# ControlDSP.net
KiCad netlist of a schematic drawn in Altium Designer
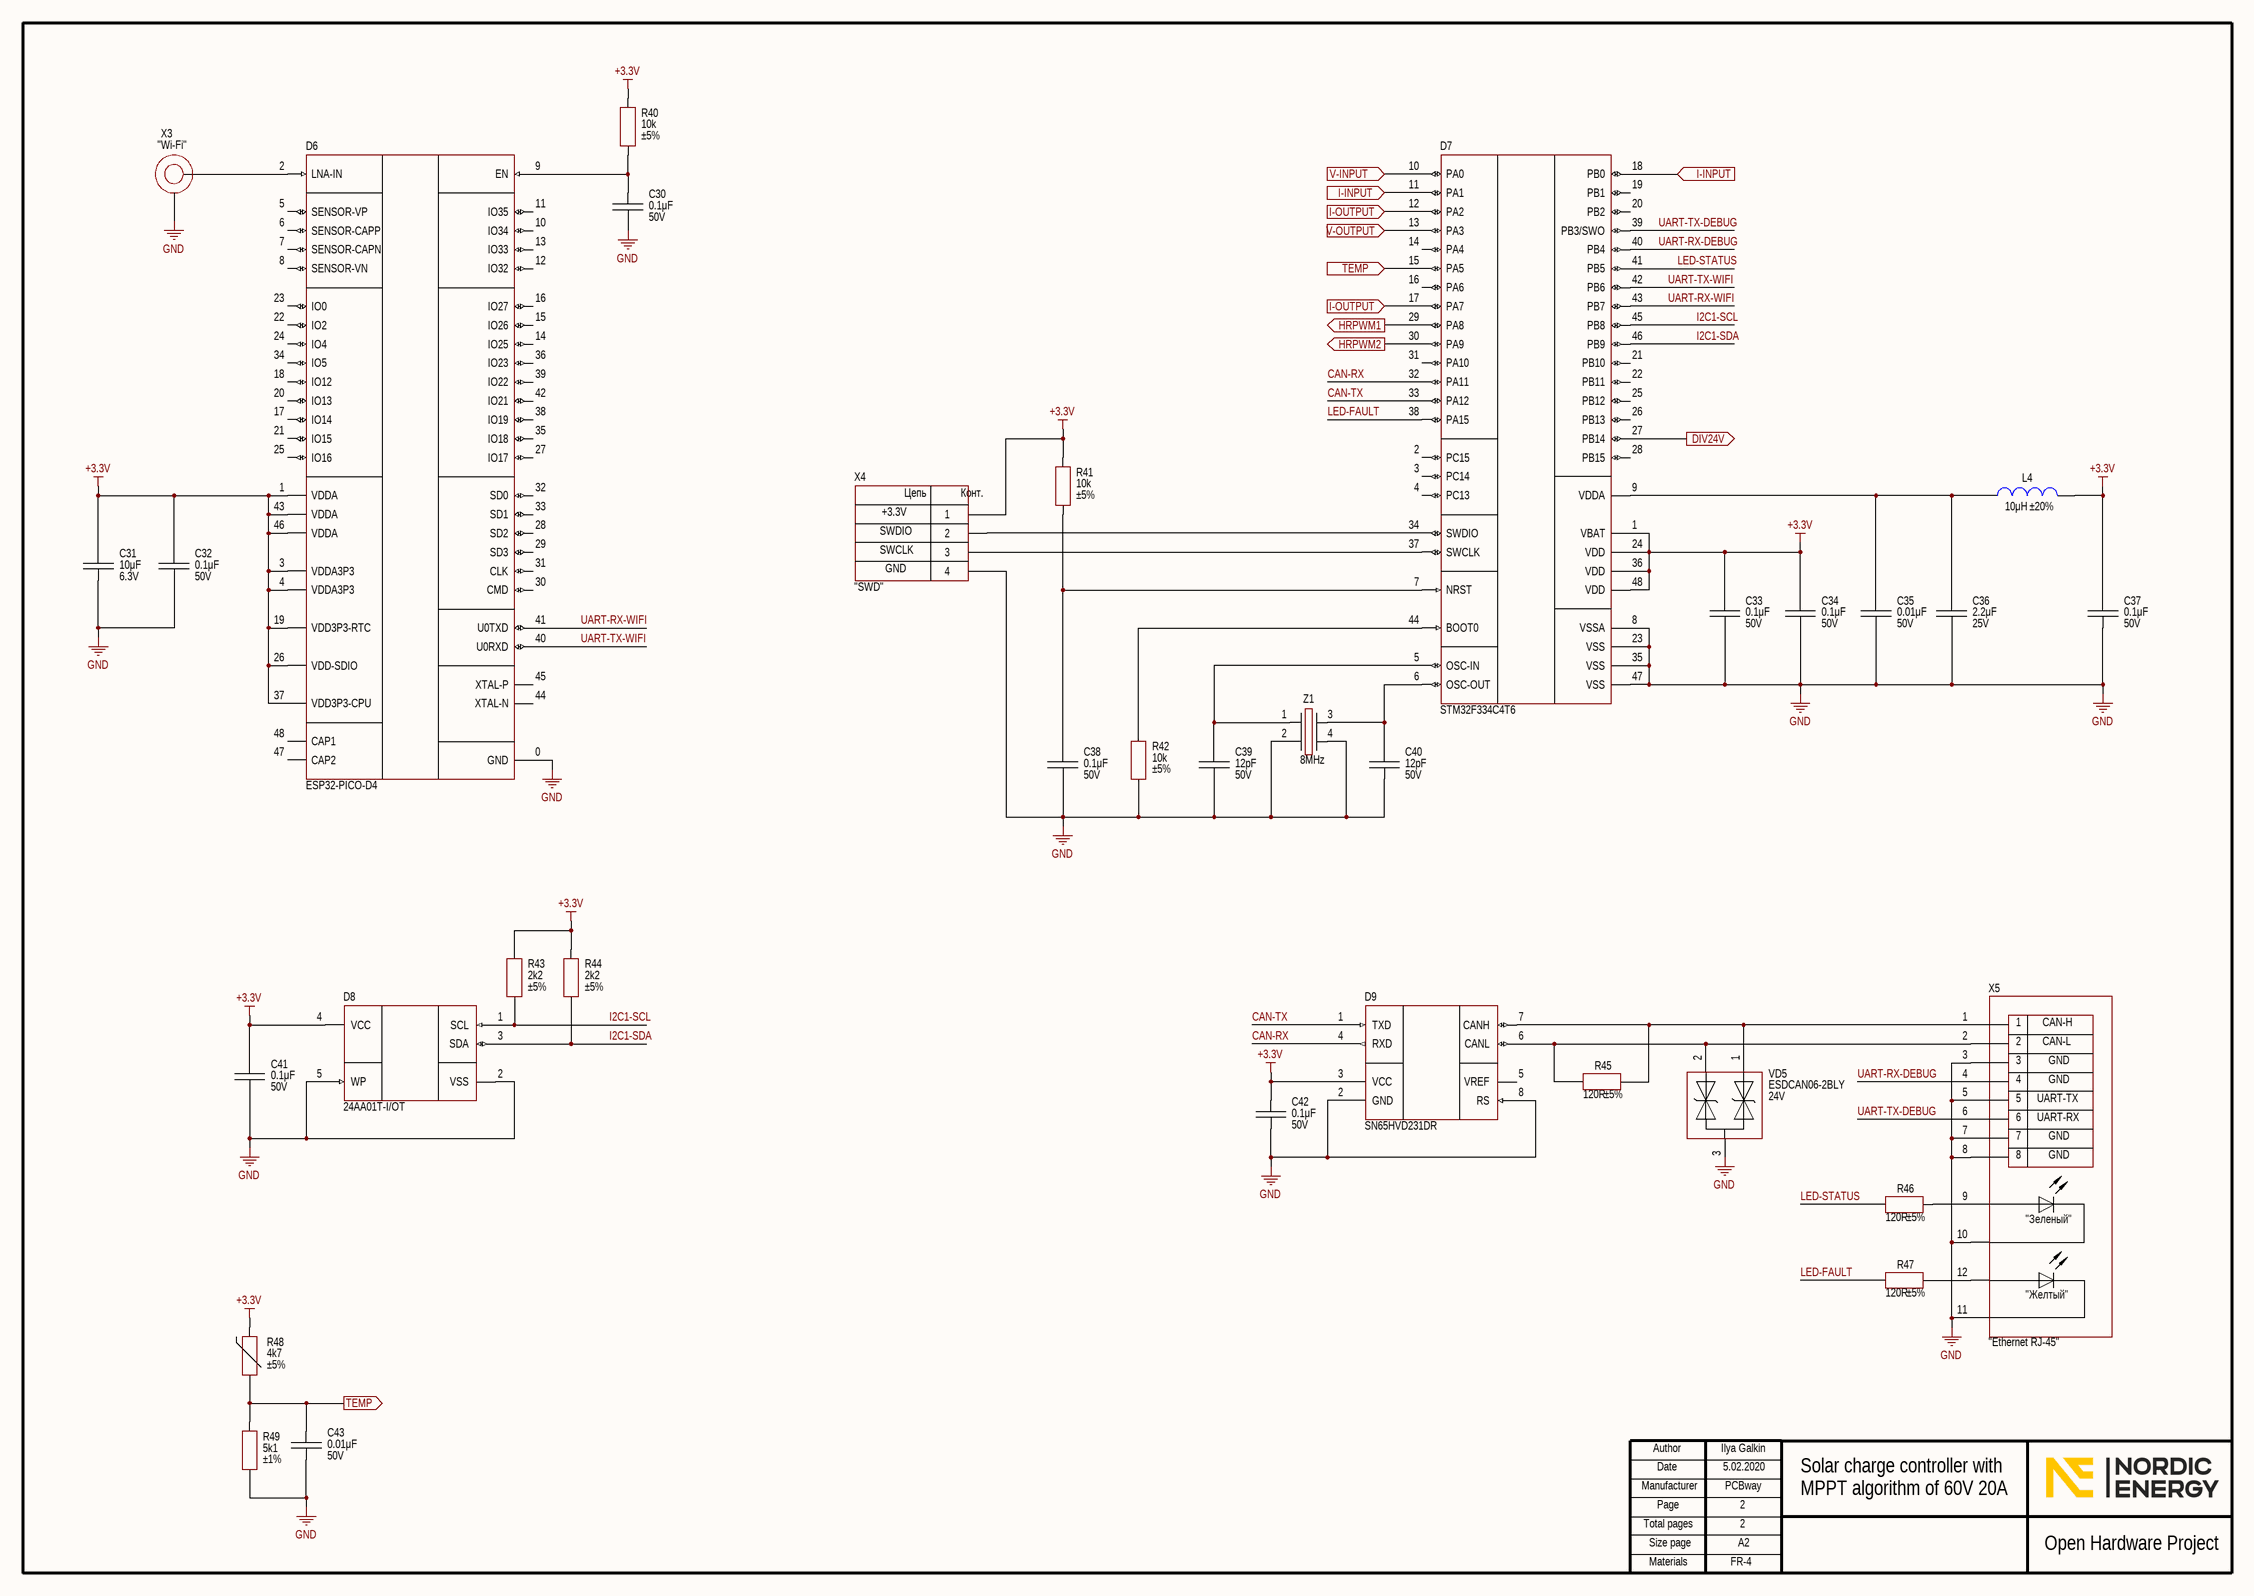
[diagram p0: ControlDSP.SchDoc]

(export (version "E")
  (design (tool "Eeschema 10.0.6"))
  (components
    (comp (ref "C30")
      (value "0.1μF")
      (footprint "CAP: 0805")
      (fields
        (field (name "MANUFACTURER") "Samsung")
        (field (name "PARTNUMBER") "CL21B104KBCNFNC")
        (field (name "VALUEMANUFACTURERPARTNUMBER") "Ceramic capacitor, 0.1μF, X7R, ±10%, 50V, 0805, -55...+125°C")
        (field (name "VOLTAGE") "50V")
      )
      (libsource (lib "Capacitor") (part "Ceramic_0805"))
    )
    (comp (ref "C31")
      (value "10μF")
      (footprint "CAP: 0805")
      (fields
        (field (name "MANUFACTURER") "Samsung")
        (field (name "PARTNUMBER") "CL21B106KQQNNNG")
        (field (name "VALUEMANUFACTURERPARTNUMBER") "Ceramic capacitor, 10μF, X7R, ±10%, 6.3V, 0805, -55...+125°C")
        (field (name "VOLTAGE") "6.3V")
      )
      (libsource (lib "Capacitor") (part "Ceramic_0805"))
    )
    (comp (ref "C32")
      (value "0.1μF")
      (footprint "CAP: 0805")
      (fields
        (field (name "MANUFACTURER") "Samsung")
        (field (name "PARTNUMBER") "CL21B104KBCNFNC")
        (field (name "VALUEMANUFACTURERPARTNUMBER") "Ceramic capacitor, 0.1μF, X7R, ±10%, 50V, 0805, -55...+125°C")
        (field (name "VOLTAGE") "50V")
      )
      (libsource (lib "Capacitor") (part "Ceramic_0805"))
    )
    (comp (ref "C33")
      (value "0.1μF")
      (footprint "CAP: 0805")
      (fields
        (field (name "MANUFACTURER") "Samsung")
        (field (name "PARTNUMBER") "CL21B104KBCNFNC")
        (field (name "VALUEMANUFACTURERPARTNUMBER") "Ceramic capacitor, 0.1μF, X7R, ±10%, 50V, 0805, -55...+125°C")
        (field (name "VOLTAGE") "50V")
      )
      (libsource (lib "Capacitor") (part "Ceramic_0805"))
    )
    (comp (ref "C34")
      (value "0.1μF")
      (footprint "CAP: 0805")
      (fields
        (field (name "MANUFACTURER") "Samsung")
        (field (name "PARTNUMBER") "CL21B104KBCNFNC")
        (field (name "VALUEMANUFACTURERPARTNUMBER") "Ceramic capacitor, 0.1μF, X7R, ±10%, 50V, 0805, -55...+125°C")
        (field (name "VOLTAGE") "50V")
      )
      (libsource (lib "Capacitor") (part "Ceramic_0805"))
    )
    (comp (ref "C35")
      (value "0.01μF")
      (footprint "CAP: 0805")
      (fields
        (field (name "MANUFACTURER") "Samsung")
        (field (name "PARTNUMBER") "CL21B103KBANNNC")
        (field (name "VALUEMANUFACTURERPARTNUMBER") "Ceramic capacitor, 0.01μF, X7R, ±10%, 50V, 0805, -55...+125°C")
        (field (name "VOLTAGE") "50V")
      )
      (libsource (lib "Capacitor") (part "Ceramic_0805"))
    )
    (comp (ref "C36")
      (value "2.2μF")
      (footprint "CAP: 0805")
      (fields
        (field (name "MANUFACTURER") "Samsung")
        (field (name "PARTNUMBER") "CL21B225KAFNFNE")
        (field (name "VALUEMANUFACTURERPARTNUMBER") "Ceramic capacitor, 2.2μF, X7R, ±10%, 25V, 0805, -55...+125°C")
        (field (name "VOLTAGE") "25V")
      )
      (libsource (lib "Capacitor") (part "Ceramic_0805"))
    )
    (comp (ref "C37")
      (value "0.1μF")
      (footprint "CAP: 0805")
      (fields
        (field (name "MANUFACTURER") "Samsung")
        (field (name "PARTNUMBER") "CL21B104KBCNFNC")
        (field (name "VALUEMANUFACTURERPARTNUMBER") "Ceramic capacitor, 0.1μF, X7R, ±10%, 50V, 0805, -55...+125°C")
        (field (name "VOLTAGE") "50V")
      )
      (libsource (lib "Capacitor") (part "Ceramic_0805"))
    )
    (comp (ref "C38")
      (value "0.1μF")
      (footprint "CAP: 0805")
      (fields
        (field (name "MANUFACTURER") "Samsung")
        (field (name "PARTNUMBER") "CL21B104KBCNFNC")
        (field (name "VALUEMANUFACTURERPARTNUMBER") "Ceramic capacitor, 0.1μF, X7R, ±10%, 50V, 0805, -55...+125°C")
        (field (name "VOLTAGE") "50V")
      )
      (libsource (lib "Capacitor") (part "Ceramic_0805"))
    )
    (comp (ref "C39")
      (value "12pF")
      (footprint "CAP: 0805")
      (fields
        (field (name "MANUFACTURER") "Samsung")
        (field (name "PARTNUMBER") "CL21C120JBANNNC")
        (field (name "VALUEMANUFACTURERPARTNUMBER") "Ceramic capacitor, 12pF, NPO, ±5%, 50V, 0805, -55...+125°C")
        (field (name "VOLTAGE") "50V")
      )
      (libsource (lib "Capacitor") (part "Ceramic_0805"))
    )
    (comp (ref "C40")
      (value "12pF")
      (footprint "CAP: 0805")
      (fields
        (field (name "MANUFACTURER") "Samsung")
        (field (name "PARTNUMBER") "CL21C120JBANNNC")
        (field (name "VALUEMANUFACTURERPARTNUMBER") "Ceramic capacitor, 12pF, NPO, ±5%, 50V, 0805, -55...+125°C")
        (field (name "VOLTAGE") "50V")
      )
      (libsource (lib "Capacitor") (part "Ceramic_0805"))
    )
    (comp (ref "C41")
      (value "0.1μF")
      (footprint "CAP: 0805")
      (fields
        (field (name "MANUFACTURER") "Samsung")
        (field (name "PARTNUMBER") "CL21B104KBCNFNC")
        (field (name "VALUEMANUFACTURERPARTNUMBER") "Ceramic capacitor, 0.1μF, X7R, ±10%, 50V, 0805, -55...+125°C")
        (field (name "VOLTAGE") "50V")
      )
      (libsource (lib "Capacitor") (part "Ceramic_0805"))
    )
    (comp (ref "C42")
      (value "0.1μF")
      (footprint "CAP: 0805")
      (fields
        (field (name "MANUFACTURER") "Samsung")
        (field (name "PARTNUMBER") "CL21B104KBCNFNC")
        (field (name "VALUEMANUFACTURERPARTNUMBER") "Ceramic capacitor, 0.1μF, X7R, ±10%, 50V, 0805, -55...+125°C")
        (field (name "VOLTAGE") "50V")
      )
      (libsource (lib "Capacitor") (part "Ceramic_0805"))
    )
    (comp (ref "C43")
      (value "0.01μF")
      (footprint "CAP: 0805")
      (fields
        (field (name "MANUFACTURER") "Samsung")
        (field (name "PARTNUMBER") "CL21B103KBANNNC")
        (field (name "VALUEMANUFACTURERPARTNUMBER") "Ceramic capacitor, 0.01μF, X7R, ±10%, 50V, 0805, -55...+125°C")
        (field (name "VOLTAGE") "50V")
      )
      (libsource (lib "Capacitor") (part "Ceramic_0805"))
    )
    (comp (ref "D6")
      (value "~")
      (footprint "48-LGA (7x7)")
      (description "Wi-Fi+BT")
      (fields (field (name "MANUFACTURER") "Espressif Systems") (field (name "PARTNUMBER") "ESP32-PICO-D4"))
      (libsource (lib "IC. RF transceiver") (part "ESP32-PICO-D4"))
    )
    (comp (ref "D7")
      (value "~")
      (footprint "48-LQFP")
      (description "Cortex-M4")
      (fields
        (field (name "MANUFACTURER") "STMicroelectronics")
        (field (name "VALUEMANUFACTURERPARTNUMBER") "IC microcontroller, 32-Bit, Cortex-M4, 72MHz, 16KB, 12KB, 2...3.6V, -40...+85°C, 48-LQFP")
        (field (name "PARTNUMBER") "STM32F334C4T6")
      )
      (libsource (lib "IC. MCU") (part "STM32F334C4T6"))
    )
    (comp (ref "D8")
      (value "~")
      (footprint "SOT23-5")
      (description "EEPROM")
      (fields
        (field (name "MANUFACTURER") "Microchip Technology")
        (field (name "VALUEMANUFACTURERPARTNUMBER") "IC memory, EEPROM, 1KB (128x8), 400 kHz, I2C, 1.7...5.5V, -40...+85°C, SOT-23-5")
        (field (name "PARTNUMBER") "24AA01T-I/OT")
      )
      (libsource (lib "IC. Memory") (part "24AA01T"))
    )
    (comp (ref "D9")
      (value "~")
      (footprint "8-SOIC")
      (description "CAN")
      (fields
        (field (name "MANUFACTURER") "Texas Instruments")
        (field (name "VALUEMANUFACTURERPARTNUMBER") "IC CAN transceiver, 1Mbps, Half-duplex, 3...3.6V, -40...+85°C, 8-SOIC")
        (field (name "PARTNUMBER") "SN65HVD231DR")
      )
      (libsource (lib "IC. Interface") (part "SN65HVD231DR"))
    )
    (comp (ref "L4")
      (value "10μH")
      (footprint "IND: 0805")
      (fields
        (field (name "MANUFACTURER") "Murata Electronics")
        (field (name "PARTNUMBER") "LQM21DH100M70L")
        (field (name "VALUEMANUFACTURERPARTNUMBER") "Fixed inductor, 10μH, ±20%, 0805, 250mA, -55...+125°C")
        (field (name "TOLERANCE") "±20%")
      )
      (libsource (lib "Inductor") (part "Inductor_0805"))
    )
    (comp (ref "R40")
      (value "10k")
      (footprint "RES: 0805")
      (fields
        (field (name "MANUFACTURER") "Yageo")
        (field (name "PARTNUMBER") "RC0805JR-0710KL")
        (field (name "VALUEMANUFACTURERPARTNUMBER") "Resistor film, 10k, ±5%, 0805, 0.125W, -55...+125°C")
        (field (name "TOLERANCE") "±5%")
      )
      (libsource (lib "Resistor") (part "Resistor_0805"))
    )
    (comp (ref "R41")
      (value "10k")
      (footprint "RES: 0805")
      (fields
        (field (name "MANUFACTURER") "Yageo")
        (field (name "PARTNUMBER") "RC0805JR-0710KL")
        (field (name "VALUEMANUFACTURERPARTNUMBER") "Resistor film, 10k, ±5%, 0805, 0.125W, -55...+125°C")
        (field (name "TOLERANCE") "±5%")
      )
      (libsource (lib "Resistor") (part "Resistor_0805"))
    )
    (comp (ref "R42")
      (value "10k")
      (footprint "RES: 0805")
      (fields
        (field (name "MANUFACTURER") "Yageo")
        (field (name "PARTNUMBER") "RC0805JR-0710KL")
        (field (name "VALUEMANUFACTURERPARTNUMBER") "Resistor film, 10k, ±5%, 0805, 0.125W, -55...+125°C")
        (field (name "TOLERANCE") "±5%")
      )
      (libsource (lib "Resistor") (part "Resistor_0805"))
    )
    (comp (ref "R43")
      (value "2k2")
      (footprint "RES: 0805")
      (fields
        (field (name "MANUFACTURER") "Yageo")
        (field (name "PARTNUMBER") "RC0805JR-072K2L")
        (field (name "VALUEMANUFACTURERPARTNUMBER") "Resistor film, 2k2, ±5%, 0805, 0.125W, -55...+125°C")
        (field (name "TOLERANCE") "±5%")
      )
      (libsource (lib "Resistor") (part "Resistor_0805"))
    )
    (comp (ref "R44")
      (value "2k2")
      (footprint "RES: 0805")
      (fields
        (field (name "MANUFACTURER") "Yageo")
        (field (name "PARTNUMBER") "RC0805JR-072K2L")
        (field (name "VALUEMANUFACTURERPARTNUMBER") "Resistor film, 2k2, ±5%, 0805, 0.125W, -55...+125°C")
        (field (name "TOLERANCE") "±5%")
      )
      (libsource (lib "Resistor") (part "Resistor_0805"))
    )
    (comp (ref "R45")
      (value "120R")
      (footprint "RES: 0805")
      (fields
        (field (name "MANUFACTURER") "Yageo")
        (field (name "PARTNUMBER") "RC0805JR-07120RL")
        (field (name "VALUEMANUFACTURERPARTNUMBER") "Resistor film, 120R, ±5%, 0805, 0.125W, -55...+125°C")
        (field (name "TOLERANCE") "±5%")
      )
      (libsource (lib "") (part "Resistor_0805_1"))
    )
    (comp (ref "R46")
      (value "120R")
      (footprint "RES: 0805")
      (fields
        (field (name "MANUFACTURER") "Yageo")
        (field (name "PARTNUMBER") "RC0805JR-07120RL")
        (field (name "VALUEMANUFACTURERPARTNUMBER") "Resistor film, 120R, ±5%, 0805, 0.125W, -55...+125°C")
        (field (name "TOLERANCE") "±5%")
      )
      (libsource (lib "") (part "Resistor_0805_1"))
    )
    (comp (ref "R47")
      (value "120R")
      (footprint "RES: 0805")
      (fields
        (field (name "MANUFACTURER") "Yageo")
        (field (name "PARTNUMBER") "RC0805JR-07120RL")
        (field (name "VALUEMANUFACTURERPARTNUMBER") "Resistor film, 120R, ±5%, 0805, 0.125W, -55...+125°C")
        (field (name "TOLERANCE") "±5%")
      )
      (libsource (lib "") (part "Resistor_0805_1"))
    )
    (comp (ref "R48")
      (value "4k7")
      (footprint "RES: 0805")
      (fields
        (field (name "MANUFACTURER") "TDK")
        (field (name "PARTNUMBER") "B57401V2472J062")
        (field (name "VALUEMANUFACTURERPARTNUMBER") "NTC resistor, 4k7, ±5%, 0805, 3650K, -55...+125°C")
        (field (name "TOLERANCE") "±5%")
      )
      (libsource (lib "Resistor") (part "NTC"))
    )
    (comp (ref "R49")
      (value "5k1")
      (footprint "RES: 0805")
      (fields
        (field (name "MANUFACTURER") "Yageo")
        (field (name "PARTNUMBER") "RC0805FR-075K1L")
        (field (name "VALUEMANUFACTURERPARTNUMBER") "Resistor film, 5k1, ±1%, 0805, 0.125W, -55...+125°C")
        (field (name "TOLERANCE") "±1%")
      )
      (libsource (lib "Resistor") (part "Resistor_0805"))
    )
    (comp (ref "VD5")
      (value "~")
      (footprint "SOT23")
      (fields
        (field (name "MANUFACTURER") "STMicroelectronics")
        (field (name "VALUEMANUFACTURERPARTNUMBER") "TVS diode, 24V, 230W peak, 3A, 13pF, SOT-23, -40...+150°C")
        (field (name "VOLTAGE") "24V")
        (field (name "PARTNUMBER") "ESDCAN06-2BLY")
      )
      (libsource (lib "Diode") (part "TVS_array"))
    )
    (comp (ref "X3")
      (value "~")
      (footprint "CON: u.Fl")
      (fields
        (field (name "MANUFACTURER") "Hirose Electric")
        (field (name "VALUEMANUFACTURERPARTNUMBER") "Connector u.FL, 50 Ohm, 6GHz")
        (field (name "PARTNUMBER") "U.FL-R-SMT(01)")
        (field (name "COMMENTTEXT") "\"Wi-Fi\"")
      )
      (libsource (lib "Connector") (part "Connector_uFL"))
    )
    (comp (ref "X4")
      (value "~")
      (footprint "CON: SM04B-GHS")
      (fields
        (field (name "MANUFACTURER") "JST")
        (field (name "VALUEMANUFACTURERPARTNUMBER") "Connector, 4pin, 1.25mm, 50VDC, 1A")
        (field (name "PARTNUMBER") "SM04B-GHS")
        (field (name "COMMENTTEXT") "\"SWD\"")
      )
      (libsource (lib "Connector") (part "Connector_SM04B"))
    )
    (comp (ref "X5")
      (value "~")
      (footprint "CON: RJ-45 (615008137421 / DS1128-09-S8B8S)")
      (fields
        (field (name "MANUFACTURER") "Wurth")
        (field (name "VALUEMANUFACTURERPARTNUMBER") "Etherner RJ-45 connector")
        (field (name "PARTNUMBER") "615008137421")
        (field (name "COMMENTTEXT") "\"Ethernet RJ-45\"")
      )
      (libsource (lib "Connector") (part "Connector_RJ45"))
    )
    (comp (ref "Z1")
      (value "~")
      (footprint "OSC: 3225")
      (fields
        (field (name "MANUFACTURER") "ECS")
        (field (name "PARTNUMBER") "ECS-80-12-33-JGN-TR")
        (field (name "VALUEMANUFACTURERPARTNUMBER") "Crystal, 8MHz, 12pF, ±30ppm, case 3225, -40...+85°C")
        (field (name "FREQUENCY") "8MHz")
      )
      (libsource (lib "Oscilator") (part "Crystal_3225"))
    )
  )
  (nets
    (net (code "1") (name "+3.3V") (class "Default")
      (node (ref "C31") (pin "2") (pinfunction "2_2") (pintype "power_in"))
      (node (ref "C32") (pin "2") (pinfunction "2_2") (pintype "power_in"))
      (node (ref "C33") (pin "2") (pinfunction "2_2") (pintype "power_in"))
      (node (ref "C34") (pin "2") (pinfunction "2_2") (pintype "power_in"))
      (node (ref "C37") (pin "2") (pinfunction "2_2") (pintype "power_in"))
      (node (ref "C41") (pin "2") (pinfunction "2_2") (pintype "power_in"))
      (node (ref "C42") (pin "2") (pinfunction "2_2") (pintype "power_in"))
      (node (ref "D6") (pin "1") (pinfunction "VDDA_1") (pintype "passive"))
      (node (ref "D6") (pin "19") (pinfunction "VDD3P3-RTC_19") (pintype "passive"))
      (node (ref "D6") (pin "26") (pinfunction "VDD-SDIO_26") (pintype "passive"))
      (node (ref "D6") (pin "3") (pinfunction "VDDA3P3_3") (pintype "passive"))
      (node (ref "D6") (pin "37") (pinfunction "VDD3P3-CPU_37") (pintype "passive"))
      (node (ref "D6") (pin "4") (pinfunction "VDDA3P3_4") (pintype "passive"))
      (node (ref "D6") (pin "43") (pinfunction "VDDA_43") (pintype "passive"))
      (node (ref "D6") (pin "46") (pinfunction "VDDA_46") (pintype "passive"))
      (node (ref "D7") (pin "1") (pinfunction "VBAT_1") (pintype "passive"))
      (node (ref "D7") (pin "24") (pinfunction "VDD_24") (pintype "passive"))
      (node (ref "D7") (pin "36") (pinfunction "VDD_36") (pintype "passive"))
      (node (ref "D7") (pin "48") (pinfunction "VDD_48") (pintype "passive"))
      (node (ref "D8") (pin "4") (pinfunction "VCC_4") (pintype "power_in"))
      (node (ref "D9") (pin "3") (pinfunction "VCC_3") (pintype "passive"))
      (node (ref "L4") (pin "1") (pinfunction "1_1") (pintype "passive"))
      (node (ref "R40") (pin "2") (pinfunction "2_2") (pintype "passive"))
      (node (ref "R41") (pin "2") (pinfunction "2_2") (pintype "passive"))
      (node (ref "R43") (pin "2") (pinfunction "2_2") (pintype "passive"))
      (node (ref "R44") (pin "2") (pinfunction "2_2") (pintype "passive"))
      (node (ref "R48") (pin "2") (pinfunction "2_2") (pintype "passive"))
      (node (ref "X4") (pin "1") (pinfunction "1_1") (pintype "passive"))
    )
    (net (code "2") (name "/CAN-RX") (class "Default")
      (node (ref "D7") (pin "32") (pinfunction "PA11_32") (pintype "bidirectional"))
      (node (ref "D9") (pin "4") (pinfunction "RXD_4") (pintype "output"))
    )
    (net (code "3") (name "/CAN-TX") (class "Default")
      (node (ref "D7") (pin "33") (pinfunction "PA12_33") (pintype "bidirectional"))
      (node (ref "D9") (pin "1") (pinfunction "TXD_1") (pintype "input"))
    )
    (net (code "4") (name "/DIV24V") (class "Default")
      (node (ref "D7") (pin "27") (pinfunction "PB14_27") (pintype "bidirectional"))
    )
    (net (code "5") (name "/HRPWM1") (class "Default")
      (node (ref "D7") (pin "29") (pinfunction "PA8_29") (pintype "bidirectional"))
    )
    (net (code "6") (name "/HRPWM2") (class "Default")
      (node (ref "D7") (pin "30") (pinfunction "PA9_30") (pintype "bidirectional"))
    )
    (net (code "7") (name "/I-INPUT") (class "Default")
      (node (ref "D7") (pin "11") (pinfunction "PA1_11") (pintype "bidirectional"))
      (node (ref "D7") (pin "18") (pinfunction "PB0_18") (pintype "bidirectional"))
    )
    (net (code "8") (name "/I-OUTPUT") (class "Default")
      (node (ref "D7") (pin "12") (pinfunction "PA2_12") (pintype "bidirectional"))
      (node (ref "D7") (pin "17") (pinfunction "PA7_17") (pintype "bidirectional"))
    )
    (net (code "9") (name "/I2C1-SCL") (class "Default")
      (node (ref "D7") (pin "45") (pinfunction "PB8_45") (pintype "bidirectional"))
      (node (ref "D8") (pin "1") (pinfunction "SCL_1") (pintype "input"))
      (node (ref "R43") (pin "1") (pinfunction "1_1") (pintype "passive"))
    )
    (net (code "10") (name "/I2C1-SDA") (class "Default")
      (node (ref "D7") (pin "46") (pinfunction "PB9_46") (pintype "bidirectional"))
      (node (ref "D8") (pin "3") (pinfunction "SDA_3") (pintype "bidirectional"))
      (node (ref "R44") (pin "1") (pinfunction "1_1") (pintype "passive"))
    )
    (net (code "11") (name "/LED-FAULT") (class "Default")
      (node (ref "D7") (pin "38") (pinfunction "PA15_38") (pintype "bidirectional"))
      (node (ref "R47") (pin "2") (pinfunction "2_2") (pintype "passive"))
    )
    (net (code "12") (name "/LED-STATUS") (class "Default")
      (node (ref "D7") (pin "41") (pinfunction "PB5_41") (pintype "bidirectional"))
      (node (ref "R46") (pin "2") (pinfunction "2_2") (pintype "passive"))
    )
    (net (code "13") (name "/TEMP") (class "Default")
      (node (ref "C43") (pin "2") (pinfunction "2_2") (pintype "power_in"))
      (node (ref "D7") (pin "15") (pinfunction "PA5_15") (pintype "bidirectional"))
      (node (ref "R48") (pin "1") (pinfunction "1_1") (pintype "passive"))
      (node (ref "R49") (pin "2") (pinfunction "2_2") (pintype "passive"))
    )
    (net (code "14") (name "/UART-RX-DEBUG") (class "Default")
      (node (ref "D7") (pin "40") (pinfunction "PB4_40") (pintype "bidirectional"))
      (node (ref "X5") (pin "4") (pinfunction "D2_4") (pintype "passive"))
    )
    (net (code "15") (name "/UART-RX-WIFI") (class "Default")
      (node (ref "D6") (pin "41") (pinfunction "U0TXD_41") (pintype "bidirectional"))
      (node (ref "D7") (pin "43") (pinfunction "PB7_43") (pintype "bidirectional"))
    )
    (net (code "16") (name "/UART-TX-DEBUG") (class "Default")
      (node (ref "D7") (pin "39") (pinfunction "PB3/SWO_39") (pintype "bidirectional"))
      (node (ref "X5") (pin "6") (pinfunction "D2_6") (pintype "passive"))
    )
    (net (code "17") (name "/UART-TX-WIFI") (class "Default")
      (node (ref "D6") (pin "40") (pinfunction "U0RXD_40") (pintype "bidirectional"))
      (node (ref "D7") (pin "42") (pinfunction "PB6_42") (pintype "bidirectional"))
    )
    (net (code "18") (name "/V-INPUT") (class "Default")
      (node (ref "D7") (pin "10") (pinfunction "PA0_10") (pintype "bidirectional"))
    )
    (net (code "19") (name "/V-OUTPUT") (class "Default")
      (node (ref "D7") (pin "13") (pinfunction "PA3_13") (pintype "bidirectional"))
    )
    (net (code "20") (name "GND") (class "Default")
      (node (ref "C30") (pin "1") (pinfunction "1_1") (pintype "power_in"))
      (node (ref "C31") (pin "1") (pinfunction "1_1") (pintype "power_in"))
      (node (ref "C32") (pin "1") (pinfunction "1_1") (pintype "power_in"))
      (node (ref "C33") (pin "1") (pinfunction "1_1") (pintype "power_in"))
      (node (ref "C34") (pin "1") (pinfunction "1_1") (pintype "power_in"))
      (node (ref "C35") (pin "1") (pinfunction "1_1") (pintype "power_in"))
      (node (ref "C36") (pin "1") (pinfunction "1_1") (pintype "power_in"))
      (node (ref "C37") (pin "1") (pinfunction "1_1") (pintype "power_in"))
      (node (ref "C38") (pin "1") (pinfunction "1_1") (pintype "power_in"))
      (node (ref "C39") (pin "1") (pinfunction "1_1") (pintype "power_in"))
      (node (ref "C40") (pin "1") (pinfunction "1_1") (pintype "power_in"))
      (node (ref "C41") (pin "1") (pinfunction "1_1") (pintype "power_in"))
      (node (ref "C42") (pin "1") (pinfunction "1_1") (pintype "power_in"))
      (node (ref "C43") (pin "1") (pinfunction "1_1") (pintype "power_in"))
      (node (ref "D6") (pin "0") (pinfunction "GND_0") (pintype "passive"))
      (node (ref "D7") (pin "23") (pinfunction "VSS_23") (pintype "passive"))
      (node (ref "D7") (pin "35") (pinfunction "VSS_35") (pintype "passive"))
      (node (ref "D7") (pin "47") (pinfunction "VSS_47") (pintype "passive"))
      (node (ref "D7") (pin "8") (pinfunction "VSSA_8") (pintype "passive"))
      (node (ref "D8") (pin "2") (pinfunction "VSS_2") (pintype "power_in"))
      (node (ref "D8") (pin "5") (pinfunction "WP_5") (pintype "input"))
      (node (ref "D9") (pin "2") (pinfunction "GND_2") (pintype "passive"))
      (node (ref "D9") (pin "8") (pinfunction "RS_8") (pintype "input"))
      (node (ref "R42") (pin "1") (pinfunction "1_1") (pintype "passive"))
      (node (ref "R49") (pin "1") (pinfunction "1_1") (pintype "passive"))
      (node (ref "VD5") (pin "3") (pintype "passive"))
      (node (ref "X3") (pin "2") (pinfunction "2_2") (pintype "passive"))
      (node (ref "X4") (pin "4") (pinfunction "4_4") (pintype "power_in"))
      (node (ref "X5") (pin "10") (pinfunction "D1_10") (pintype "passive"))
      (node (ref "X5") (pin "11") (pinfunction "D3_11") (pintype "passive"))
      (node (ref "X5") (pin "3") (pinfunction "D2_3") (pintype "passive"))
      (node (ref "X5") (pin "5") (pinfunction "D2_5") (pintype "passive"))
      (node (ref "X5") (pin "7") (pinfunction "D2_7") (pintype "passive"))
      (node (ref "X5") (pin "8") (pinfunction "D2_8") (pintype "passive"))
      (node (ref "Z1") (pin "2") (pinfunction "2_2") (pintype "passive"))
      (node (ref "Z1") (pin "4") (pinfunction "4_4") (pintype "passive"))
    )
    (net (code "21") (name "Net-(D6-EN)") (class "Default")
      (node (ref "C30") (pin "2") (pinfunction "2_2") (pintype "power_in"))
      (node (ref "D6") (pin "9") (pinfunction "EN_9") (pintype "input"))
      (node (ref "R40") (pin "1") (pinfunction "1_1") (pintype "passive"))
    )
    (net (code "22") (name "Net-(D6-LNA-IN)") (class "Default")
      (node (ref "D6") (pin "2") (pinfunction "LNA-IN_2") (pintype "input"))
      (node (ref "X3") (pin "1") (pinfunction "1_1") (pintype "passive"))
    )
    (net (code "23") (name "Net-(D7-BOOT0)") (class "Default")
      (node (ref "D7") (pin "44") (pinfunction "BOOT0_44") (pintype "input"))
      (node (ref "R42") (pin "2") (pinfunction "2_2") (pintype "passive"))
    )
    (net (code "24") (name "Net-(D7-NRST)") (class "Default")
      (node (ref "C38") (pin "2") (pinfunction "2_2") (pintype "power_in"))
      (node (ref "D7") (pin "7") (pinfunction "NRST_7") (pintype "input"))
      (node (ref "R41") (pin "1") (pinfunction "1_1") (pintype "passive"))
    )
    (net (code "25") (name "Net-(D7-OSC-IN)") (class "Default")
      (node (ref "C39") (pin "2") (pinfunction "2_2") (pintype "power_in"))
      (node (ref "D7") (pin "5") (pinfunction "OSC-IN_5") (pintype "bidirectional"))
      (node (ref "Z1") (pin "1") (pinfunction "1_1") (pintype "passive"))
    )
    (net (code "26") (name "Net-(D7-OSC-OUT)") (class "Default")
      (node (ref "C40") (pin "2") (pinfunction "2_2") (pintype "power_in"))
      (node (ref "D7") (pin "6") (pinfunction "OSC-OUT_6") (pintype "bidirectional"))
      (node (ref "Z1") (pin "3") (pinfunction "3_3") (pintype "passive"))
    )
    (net (code "27") (name "Net-(D7-SWCLK)") (class "Default")
      (node (ref "D7") (pin "37") (pinfunction "SWCLK_37") (pintype "bidirectional"))
      (node (ref "X4") (pin "3") (pinfunction "3_3") (pintype "power_in"))
    )
    (net (code "28") (name "Net-(D7-SWDIO)") (class "Default")
      (node (ref "D7") (pin "34") (pinfunction "SWDIO_34") (pintype "bidirectional"))
      (node (ref "X4") (pin "2") (pinfunction "2_2") (pintype "passive"))
    )
    (net (code "29") (name "Net-(D7-VDDA)") (class "Default")
      (node (ref "C35") (pin "2") (pinfunction "2_2") (pintype "power_in"))
      (node (ref "C36") (pin "2") (pinfunction "2_2") (pintype "power_in"))
      (node (ref "D7") (pin "9") (pinfunction "VDDA_9") (pintype "passive"))
      (node (ref "L4") (pin "2") (pinfunction "2_2") (pintype "passive"))
    )
    (net (code "30") (name "Net-(D9-CANH)") (class "Default")
      (node (ref "D9") (pin "7") (pinfunction "CANH_7") (pintype "bidirectional"))
      (node (ref "R45") (pin "1") (pinfunction "1_1") (pintype "passive"))
      (node (ref "VD5") (pin "1") (pintype "passive"))
      (node (ref "X5") (pin "1") (pinfunction "D2_1") (pintype "passive"))
    )
    (net (code "31") (name "Net-(D9-CANL)") (class "Default")
      (node (ref "D9") (pin "6") (pinfunction "CANL_6") (pintype "bidirectional"))
      (node (ref "R45") (pin "2") (pinfunction "2_2") (pintype "passive"))
      (node (ref "VD5") (pin "2") (pintype "passive"))
      (node (ref "X5") (pin "2") (pinfunction "D2_2") (pintype "passive"))
    )
    (net (code "32") (name "Net-(R46-Pad1)") (class "Default")
      (node (ref "R46") (pin "1") (pinfunction "1_1") (pintype "passive"))
      (node (ref "X5") (pin "9") (pinfunction "D2_9") (pintype "passive"))
    )
    (net (code "33") (name "Net-(X5-D4)") (class "Default")
      (node (ref "R47") (pin "1") (pinfunction "1_1") (pintype "passive"))
      (node (ref "X5") (pin "12") (pinfunction "D4_12") (pintype "passive"))
    )
    (net (code "34") (name "unconnected-(D6-CAP1-Pad48)") (class "Default")
      (node (ref "D6") (pin "48") (pinfunction "CAP1_48") (pintype "passive"))
    )
    (net (code "35") (name "unconnected-(D6-CAP2-Pad47)") (class "Default")
      (node (ref "D6") (pin "47") (pinfunction "CAP2_47") (pintype "passive"))
    )
    (net (code "36") (name "unconnected-(D6-CLK-Pad31)") (class "Default")
      (node (ref "D6") (pin "31") (pinfunction "CLK_31") (pintype "bidirectional"))
    )
    (net (code "37") (name "unconnected-(D6-CMD-Pad30)") (class "Default")
      (node (ref "D6") (pin "30") (pinfunction "CMD_30") (pintype "bidirectional"))
    )
    (net (code "38") (name "unconnected-(D6-IO0-Pad23)") (class "Default")
      (node (ref "D6") (pin "23") (pinfunction "IO0_23") (pintype "bidirectional"))
    )
    (net (code "39") (name "unconnected-(D6-IO2-Pad22)") (class "Default")
      (node (ref "D6") (pin "22") (pinfunction "IO2_22") (pintype "bidirectional"))
    )
    (net (code "40") (name "unconnected-(D6-IO4-Pad24)") (class "Default")
      (node (ref "D6") (pin "24") (pinfunction "IO4_24") (pintype "bidirectional"))
    )
    (net (code "41") (name "unconnected-(D6-IO5-Pad34)") (class "Default")
      (node (ref "D6") (pin "34") (pinfunction "IO5_34") (pintype "bidirectional"))
    )
    (net (code "42") (name "unconnected-(D6-IO12-Pad18)") (class "Default")
      (node (ref "D6") (pin "18") (pinfunction "IO12_18") (pintype "bidirectional"))
    )
    (net (code "43") (name "unconnected-(D6-IO13-Pad20)") (class "Default")
      (node (ref "D6") (pin "20") (pinfunction "IO13_20") (pintype "bidirectional"))
    )
    (net (code "44") (name "unconnected-(D6-IO14-Pad17)") (class "Default")
      (node (ref "D6") (pin "17") (pinfunction "IO14_17") (pintype "bidirectional"))
    )
    (net (code "45") (name "unconnected-(D6-IO15-Pad21)") (class "Default")
      (node (ref "D6") (pin "21") (pinfunction "IO15_21") (pintype "bidirectional"))
    )
    (net (code "46") (name "unconnected-(D6-IO16-Pad25)") (class "Default")
      (node (ref "D6") (pin "25") (pinfunction "IO16_25") (pintype "bidirectional"))
    )
    (net (code "47") (name "unconnected-(D6-IO17-Pad27)") (class "Default")
      (node (ref "D6") (pin "27") (pinfunction "IO17_27") (pintype "bidirectional"))
    )
    (net (code "48") (name "unconnected-(D6-IO18-Pad35)") (class "Default")
      (node (ref "D6") (pin "35") (pinfunction "IO18_35") (pintype "bidirectional"))
    )
    (net (code "49") (name "unconnected-(D6-IO19-Pad38)") (class "Default")
      (node (ref "D6") (pin "38") (pinfunction "IO19_38") (pintype "bidirectional"))
    )
    (net (code "50") (name "unconnected-(D6-IO21-Pad42)") (class "Default")
      (node (ref "D6") (pin "42") (pinfunction "IO21_42") (pintype "bidirectional"))
    )
    (net (code "51") (name "unconnected-(D6-IO22-Pad39)") (class "Default")
      (node (ref "D6") (pin "39") (pinfunction "IO22_39") (pintype "bidirectional"))
    )
    (net (code "52") (name "unconnected-(D6-IO23-Pad36)") (class "Default")
      (node (ref "D6") (pin "36") (pinfunction "IO23_36") (pintype "bidirectional"))
    )
    (net (code "53") (name "unconnected-(D6-IO25-Pad14)") (class "Default")
      (node (ref "D6") (pin "14") (pinfunction "IO25_14") (pintype "bidirectional"))
    )
    (net (code "54") (name "unconnected-(D6-IO26-Pad15)") (class "Default")
      (node (ref "D6") (pin "15") (pinfunction "IO26_15") (pintype "bidirectional"))
    )
    (net (code "55") (name "unconnected-(D6-IO27-Pad16)") (class "Default")
      (node (ref "D6") (pin "16") (pinfunction "IO27_16") (pintype "bidirectional"))
    )
    (net (code "56") (name "unconnected-(D6-IO32-Pad12)") (class "Default")
      (node (ref "D6") (pin "12") (pinfunction "IO32_12") (pintype "bidirectional"))
    )
    (net (code "57") (name "unconnected-(D6-IO33-Pad13)") (class "Default")
      (node (ref "D6") (pin "13") (pinfunction "IO33_13") (pintype "bidirectional"))
    )
    (net (code "58") (name "unconnected-(D6-IO34-Pad10)") (class "Default")
      (node (ref "D6") (pin "10") (pinfunction "IO34_10") (pintype "bidirectional"))
    )
    (net (code "59") (name "unconnected-(D6-IO35-Pad11)") (class "Default")
      (node (ref "D6") (pin "11") (pinfunction "IO35_11") (pintype "bidirectional"))
    )
    (net (code "60") (name "unconnected-(D6-SD0-Pad32)") (class "Default")
      (node (ref "D6") (pin "32") (pinfunction "SD0_32") (pintype "bidirectional"))
    )
    (net (code "61") (name "unconnected-(D6-SD1-Pad33)") (class "Default")
      (node (ref "D6") (pin "33") (pinfunction "SD1_33") (pintype "bidirectional"))
    )
    (net (code "62") (name "unconnected-(D6-SD2-Pad28)") (class "Default")
      (node (ref "D6") (pin "28") (pinfunction "SD2_28") (pintype "bidirectional"))
    )
    (net (code "63") (name "unconnected-(D6-SD3-Pad29)") (class "Default")
      (node (ref "D6") (pin "29") (pinfunction "SD3_29") (pintype "bidirectional"))
    )
    (net (code "64") (name "unconnected-(D6-SENSOR-CAPN-Pad7)") (class "Default")
      (node (ref "D6") (pin "7") (pinfunction "SENSOR-CAPN_7") (pintype "bidirectional"))
    )
    (net (code "65") (name "unconnected-(D6-SENSOR-CAPP-Pad6)") (class "Default")
      (node (ref "D6") (pin "6") (pinfunction "SENSOR-CAPP_6") (pintype "bidirectional"))
    )
    (net (code "66") (name "unconnected-(D6-SENSOR-VN-Pad8)") (class "Default")
      (node (ref "D6") (pin "8") (pinfunction "SENSOR-VN_8") (pintype "bidirectional"))
    )
    (net (code "67") (name "unconnected-(D6-SENSOR-VP-Pad5)") (class "Default")
      (node (ref "D6") (pin "5") (pinfunction "SENSOR-VP_5") (pintype "bidirectional"))
    )
    (net (code "68") (name "unconnected-(D6-XTAL-N-Pad44)") (class "Default")
      (node (ref "D6") (pin "44") (pinfunction "XTAL-N_44") (pintype "passive"))
    )
    (net (code "69") (name "unconnected-(D6-XTAL-P-Pad45)") (class "Default")
      (node (ref "D6") (pin "45") (pinfunction "XTAL-P_45") (pintype "passive"))
    )
    (net (code "70") (name "unconnected-(D7-PA4-Pad14)") (class "Default")
      (node (ref "D7") (pin "14") (pinfunction "PA4_14") (pintype "bidirectional"))
    )
    (net (code "71") (name "unconnected-(D7-PA6-Pad16)") (class "Default")
      (node (ref "D7") (pin "16") (pinfunction "PA6_16") (pintype "bidirectional"))
    )
    (net (code "72") (name "unconnected-(D7-PA10-Pad31)") (class "Default")
      (node (ref "D7") (pin "31") (pinfunction "PA10_31") (pintype "bidirectional"))
    )
    (net (code "73") (name "unconnected-(D7-PB1-Pad19)") (class "Default")
      (node (ref "D7") (pin "19") (pinfunction "PB1_19") (pintype "bidirectional"))
    )
    (net (code "74") (name "unconnected-(D7-PB2-Pad20)") (class "Default")
      (node (ref "D7") (pin "20") (pinfunction "PB2_20") (pintype "bidirectional"))
    )
    (net (code "75") (name "unconnected-(D7-PB10-Pad21)") (class "Default")
      (node (ref "D7") (pin "21") (pinfunction "PB10_21") (pintype "bidirectional"))
    )
    (net (code "76") (name "unconnected-(D7-PB11-Pad22)") (class "Default")
      (node (ref "D7") (pin "22") (pinfunction "PB11_22") (pintype "bidirectional"))
    )
    (net (code "77") (name "unconnected-(D7-PB12-Pad25)") (class "Default")
      (node (ref "D7") (pin "25") (pinfunction "PB12_25") (pintype "bidirectional"))
    )
    (net (code "78") (name "unconnected-(D7-PB13-Pad26)") (class "Default")
      (node (ref "D7") (pin "26") (pinfunction "PB13_26") (pintype "bidirectional"))
    )
    (net (code "79") (name "unconnected-(D7-PB15-Pad28)") (class "Default")
      (node (ref "D7") (pin "28") (pinfunction "PB15_28") (pintype "bidirectional"))
    )
    (net (code "80") (name "unconnected-(D7-PC13-Pad4)") (class "Default")
      (node (ref "D7") (pin "4") (pinfunction "PC13_4") (pintype "bidirectional"))
    )
    (net (code "81") (name "unconnected-(D7-PC14-Pad3)") (class "Default")
      (node (ref "D7") (pin "3") (pinfunction "PC14_3") (pintype "bidirectional"))
    )
    (net (code "82") (name "unconnected-(D7-PC15-Pad2)") (class "Default")
      (node (ref "D7") (pin "2") (pinfunction "PC15_2") (pintype "bidirectional"))
    )
    (net (code "83") (name "unconnected-(D9-VREF-Pad5)") (class "Default")
      (node (ref "D9") (pin "5") (pinfunction "VREF_5") (pintype "passive"))
    )
  )
)
